# 19-Power-P5V.net
KiCad netlist of a schematic drawn in Altium Designer
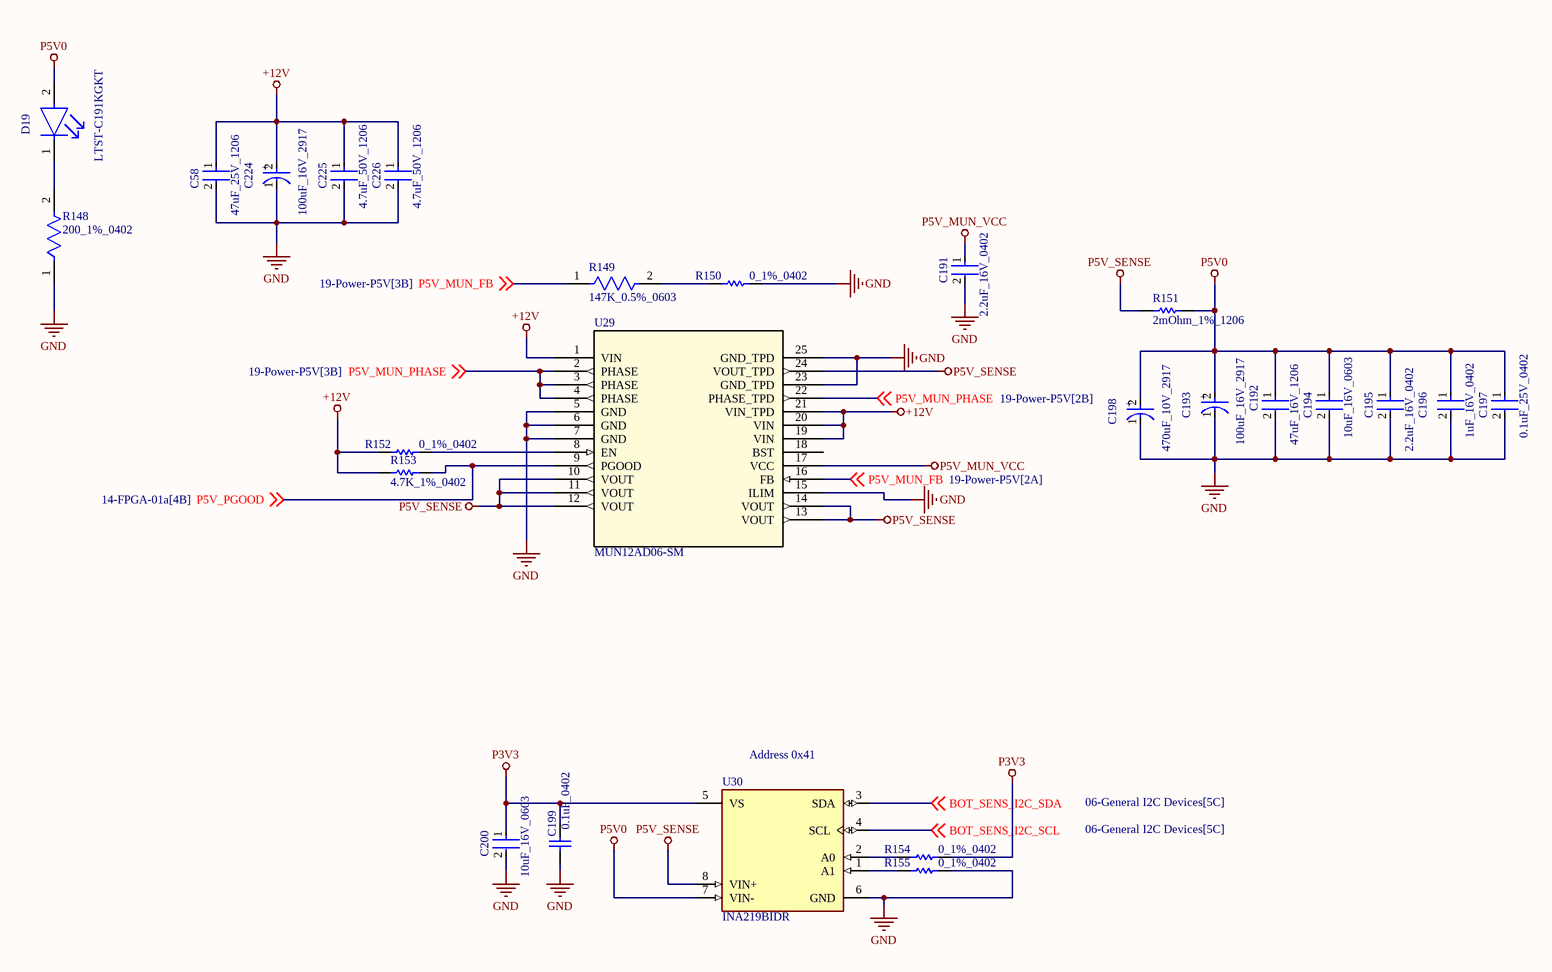
[diagram p0: 19-Power-P5V.SchDoc]

(export (version "E")
  (design (tool "Eeschema 10.0.6"))
  (components
    (comp (ref "C58")
      (value "47uF_25V_1206")
      (footprint "FP-C3216-160-0_2-MFG")
      (description "Multilayer Ceramic Capacitors 47uF ±20% 25V X5R SMD 1206")
      (fields (field (name "VOLTAGE") "25V") (field (name "TOLERANCE") "20%"))
      (libsource (lib "Altium Content Vault") (part "11868f565c42a9108669ba33697ecf6"))
    )
    (comp (ref "C191")
      (value "2.2uF_16V_0402")
      (footprint "FP-C1005-050-0_05-IPC_A")
      (description "Multilayer Ceramic Capacitors 2.2μF ±10% 16V X5R SMD 0402")
      (fields (field (name "TOLERANCE") "10%"))
      (libsource (lib "Altium Content Vault") (part "b4654b650e69147ec39a6b967a45e02"))
    )
    (comp (ref "C192")
      (value "47uF_16V_1206")
      (footprint "FP-C3216-160-0_2-MFG")
      (description "Multilayer Ceramic Capacitors 47uF ±20% 16V X5R SMD 1206")
      (fields (field (name "TOLERANCE") "20%"))
      (libsource (lib "Altium Content Vault") (part "11868f565c42a9108669ba33697ecf6"))
    )
    (comp (ref "C193")
      (value "100uF_16V_2917")
      (footprint "FP-T495D107K016ATE125-MFG")
      (description "CAP TANT 100UF 10% 16V 2917")
      (fields (field (name "VOLTAGE") "16V") (field (name "TOLERANCE") "10%"))
      (libsource (lib "Altium Content Vault") (part "a00bbbee19879c290e62620ae7e47b1"))
    )
    (comp (ref "C194")
      (value "10uF_16V_0603")
      (footprint "FP-0603-L_1_6_0_2-W_0_8_0-MFG")
      (description "Multilayer Ceramic Capacitor 10uF 16V X5R 20% SMD 0603 T/R")
      (fields (field (name "TOLERANCE") "20%"))
      (libsource (lib "Altium Content Vault") (part "b4654b650e69147ec39a6b967a45e02"))
    )
    (comp (ref "C195")
      (value "2.2uF_16V_0402")
      (footprint "FP-C1005-050-0_05-IPC_A")
      (description "Multilayer Ceramic Capacitors 2.2μF ±10% 16V X5R SMD 0402")
      (fields (field (name "TOLERANCE") "10%"))
      (libsource (lib "Altium Content Vault") (part "b4654b650e69147ec39a6b967a45e02"))
    )
    (comp (ref "C196")
      (value "1uF_16V_0402")
      (footprint "FP-0402-L_1_0_0_05-W_0_5-IPC_A")
      (description "None")
      (fields (field (name "TOLERANCE") "10%"))
      (libsource (lib "Altium Content Vault") (part "b4654b650e69147ec39a6b967a45e02"))
    )
    (comp (ref "C197")
      (value "0.1uF_25V_0402")
      (footprint "FP-0402-L_1_0_1-W_0_5_0_1-IPC_C")
      (description "General Purpose Ceramic Capacitor, 0402, 100nF, 10%, X7R, 15%, 25V")
      (fields (field (name "VOLTAGE") "25V") (field (name "TOLERANCE") "10%"))
      (libsource (lib "Altium Content Vault") (part "b4654b650e69147ec39a6b967a45e02"))
    )
    (comp (ref "C198")
      (value "470uF_10V_2917")
      (footprint "FP-TAJE-MFG")
      (description "470uF 10V  ±10% 500mΩ 2917  SMD Tantalum Capacitor")
      (fields (field (name "TOLERANCE") "10%") (field (name "VOLTAGE") "10V"))
      (libsource (lib "Altium Content Vault") (part "203bc49f2ac43e59fd269a8c329ed05"))
    )
    (comp (ref "C199")
      (value "0.1uF_0402")
      (footprint "CAPC1005X56X25NL10T15")
      (fields
        (field (name "PART NUMBER") "LD02YD104KAB2A")
        (field (name "MANUFACTURER") "AVX Interconnect / Elco")
      )
      (libsource (lib "Altium Content Vault") (part "CAP"))
    )
    (comp (ref "C200")
      (value "10uF_16V_0603")
      (footprint "FP-0603-L_1_6_0_2-W_0_8_0-MFG")
      (description "Multilayer Ceramic Capacitor 10uF 16V X5R 20% SMD 0603 T/R")
      (fields (field (name "TOLERANCE") "20%"))
      (libsource (lib "Altium Content Vault") (part "b4654b650e69147ec39a6b967a45e02"))
    )
    (comp (ref "C224")
      (value "100uF_16V_2917")
      (footprint "FP-T495D107K016ATE125-MFG")
      (description "CAP TANT 100UF 10% 16V 2917")
      (fields (field (name "VOLTAGE") "16V") (field (name "TOLERANCE") "10%"))
      (libsource (lib "Altium Content Vault") (part "a00bbbee19879c290e62620ae7e47b1"))
    )
    (comp (ref "C225")
      (value "4.7uF_50V_1206")
      (footprint "FP-GRM31C-0_2-e0_3_0_8-IPC_C")
      (description "Chip Multilayer Ceramic Capacitors for General Purpose, 1206, 4.7uF, X7R, 15%, 10%, 50V")
      (fields (field (name "VOLTAGE") "50V") (field (name "TOLERANCE") "10%"))
      (libsource (lib "Altium Content Vault") (part "02cd4be3c70576c341d710602a673aa"))
    )
    (comp (ref "C226")
      (value "4.7uF_50V_1206")
      (footprint "FP-GRM31C-0_2-e0_3_0_8-IPC_C")
      (description "Chip Multilayer Ceramic Capacitors for General Purpose, 1206, 4.7uF, X7R, 15%, 10%, 50V")
      (fields (field (name "VOLTAGE") "50V") (field (name "TOLERANCE") "10%"))
      (libsource (lib "Altium Content Vault") (part "02cd4be3c70576c341d710602a673aa"))
    )
    (comp (ref "D19")
      (value "LTST-C191KGKT")
      (footprint "FP-LTST-C191KGKT-MFG")
      (description "LED GREEN CLEAR SMD")
      (libsource (lib "Altium Content Vault") (part "8706943c75ba83719d021d2fdc84c58"))
    )
    (comp (ref "R148")
      (value "200_1%_0402")
      (footprint "FP-ERJ2RK-IPC_A")
      (description "RES SMD 200 OHM 1% 1/10W 0402")
      (fields (field (name "TOLERANCE") "1%"))
      (libsource (lib "Altium Content Vault") (part "1029c3af85768c4190bb7ad29bc67b5"))
    )
    (comp (ref "R149")
      (value "147K_0.5%_0603")
      (footprint "FP-RR0816-IPC_C")
      (description "147kΩ ±0.5% 0.0625W 1/16W Chip Resistor 0603 (1608 Metric) Thin Film")
      (fields (field (name "TOLERANCE") "0.5%"))
      (libsource (lib "Altium Content Vault") (part "1029c3af85768c4190bb7ad29bc67b5"))
    )
    (comp (ref "R150")
      (value "0_1%_0402")
      (footprint "RESC1005X40X25LL05T05")
      (description "Chip Resistor, 0 Ohm, 0.1 W, -55 to 155 degC, 0402 (1005 Metric), RoHS, Tape and Reel")
      (fields (field (name "MANUFACTURER") "Panasonic") (field (name "TOLERANCE") "5%"))
      (libsource (lib "Altium Content Vault") (part "RES-2"))
    )
    (comp (ref "R151")
      (value "2mOhm_1%_1206")
      (footprint "RESC3216X89X64NL25T25")
      (fields (field (name "MANUFACTURER") "Vishay Dale") (field (name "PART NUMBER") "WSL12062L000FEA18"))
      (libsource (lib "Altium Content Vault") (part "RES"))
    )
    (comp (ref "R152")
      (value "0_1%_0402")
      (footprint "RESC1005X40X25LL05T05")
      (description "Chip Resistor, 0 Ohm, 0.1 W, -55 to 155 degC, 0402 (1005 Metric), RoHS, Tape and Reel")
      (fields (field (name "MANUFACTURER") "Panasonic") (field (name "TOLERANCE") "5%"))
      (libsource (lib "Altium Content Vault") (part "RES-2"))
    )
    (comp (ref "R153")
      (value "4.7K_1%_0402")
      (footprint "RESC1005X40X25NL10T10")
      (fields (field (name "MANUFACTURER") "Bourns") (field (name "PART NUMBER") "CR0402-FX-4701GLF"))
      (libsource (lib "Altium Content Vault") (part "RES"))
    )
    (comp (ref "R154")
      (value "0_1%_0402")
      (footprint "RESC1005X40X25LL05T05")
      (description "Chip Resistor, 0 Ohm, 0.1 W, -55 to 155 degC, 0402 (1005 Metric), RoHS, Tape and Reel")
      (fields (field (name "MANUFACTURER") "Panasonic") (field (name "TOLERANCE") "5%"))
      (libsource (lib "Altium Content Vault") (part "RES-2"))
    )
    (comp (ref "R155")
      (value "0_1%_0402")
      (footprint "RESC1005X40X25LL05T05")
      (description "Chip Resistor, 0 Ohm, 0.1 W, -55 to 155 degC, 0402 (1005 Metric), RoHS, Tape and Reel")
      (fields (field (name "MANUFACTURER") "Panasonic") (field (name "TOLERANCE") "5%"))
      (libsource (lib "Altium Content Vault") (part "RES-2"))
    )
    (comp (ref "U29")
      (value "MUN12AD06-SM")
      (footprint "MUN12AD06-SM_CYN")
      (description "No Description Available")
      (libsource (lib "MUN12AD06-SM") (part "MUN12AD06-SM"))
    )
    (comp (ref "U30")
      (value "INA219BIDR")
      (footprint "FP-D0008A-MFG")
      (description "IC MONITOR PWR/CURR BIDIR 8-SOIC")
      (libsource (lib "Altium Content Vault") (part "41cc1aee4cbc9fa2660a15773fa0e79"))
    )
  )
  (nets
    (net (code "1") (name "+12V") (class "Default")
      (node (ref "C224") (pin "2") (pinfunction "A_2") (pintype "passive"))
      (node (ref "C225") (pin "1") (pinfunction "1_1") (pintype "passive"))
      (node (ref "C226") (pin "1") (pinfunction "1_1") (pintype "passive"))
      (node (ref "C58") (pin "1") (pinfunction "1_1") (pintype "passive"))
      (node (ref "R152") (pin "1") (pinfunction "1_1") (pintype "passive"))
      (node (ref "R153") (pin "2") (pinfunction "2_2") (pintype "passive"))
      (node (ref "U29") (pin "1") (pinfunction "VIN_1") (pintype "power_in"))
      (node (ref "U29") (pin "19") (pinfunction "VIN_19") (pintype "power_in"))
      (node (ref "U29") (pin "20") (pinfunction "VIN_20") (pintype "power_in"))
      (node (ref "U29") (pin "21") (pinfunction "VIN_TPD_21") (pintype "power_in"))
    )
    (net (code "2") (name "BOT_SENS_I2C_SCL") (class "Default")
      (node (ref "U30") (pin "4") (pinfunction "SCL_4") (pintype "bidirectional"))
    )
    (net (code "3") (name "BOT_SENS_I2C_SDA") (class "Default")
      (node (ref "U30") (pin "3") (pinfunction "SDA_3") (pintype "bidirectional"))
    )
    (net (code "4") (name "GND") (class "Default")
      (node (ref "C191") (pin "2") (pinfunction "2_2") (pintype "passive"))
      (node (ref "C192") (pin "2") (pinfunction "2_2") (pintype "passive"))
      (node (ref "C193") (pin "1") (pinfunction "C_1") (pintype "passive"))
      (node (ref "C194") (pin "2") (pinfunction "2_2") (pintype "passive"))
      (node (ref "C195") (pin "2") (pinfunction "2_2") (pintype "passive"))
      (node (ref "C196") (pin "2") (pinfunction "2_2") (pintype "passive"))
      (node (ref "C197") (pin "2") (pinfunction "2_2") (pintype "passive"))
      (node (ref "C198") (pin "1") (pinfunction "C_1") (pintype "passive"))
      (node (ref "C199") (pin "1") (pinfunction "1_1") (pintype "passive"))
      (node (ref "C200") (pin "2") (pinfunction "2_2") (pintype "passive"))
      (node (ref "C224") (pin "1") (pinfunction "C_1") (pintype "passive"))
      (node (ref "C225") (pin "2") (pinfunction "2_2") (pintype "passive"))
      (node (ref "C226") (pin "2") (pinfunction "2_2") (pintype "passive"))
      (node (ref "C58") (pin "2") (pinfunction "2_2") (pintype "passive"))
      (node (ref "R148") (pin "1") (pinfunction "1_1") (pintype "passive"))
      (node (ref "R150") (pin "2") (pinfunction "2_2") (pintype "passive"))
      (node (ref "R155") (pin "2") (pinfunction "2_2") (pintype "passive"))
      (node (ref "U29") (pin "15") (pinfunction "ILIM_15") (pintype "passive"))
      (node (ref "U29") (pin "23") (pinfunction "GND_TPD_23") (pintype "power_in"))
      (node (ref "U29") (pin "25") (pinfunction "GND_TPD_25") (pintype "power_in"))
      (node (ref "U29") (pin "5") (pinfunction "GND_5") (pintype "power_in"))
      (node (ref "U29") (pin "6") (pinfunction "GND_6") (pintype "power_in"))
      (node (ref "U29") (pin "7") (pinfunction "GND_7") (pintype "power_in"))
      (node (ref "U30") (pin "6") (pinfunction "GND_6") (pintype "power_in"))
    )
    (net (code "5") (name "Net-(D19-C)") (class "Default")
      (node (ref "D19") (pin "1") (pinfunction "C_1") (pintype "passive"))
      (node (ref "R148") (pin "2") (pinfunction "2_2") (pintype "passive"))
    )
    (net (code "6") (name "Net-(R149-Pad2)") (class "Default")
      (node (ref "R149") (pin "2") (pinfunction "2_2") (pintype "passive"))
      (node (ref "R150") (pin "1") (pinfunction "1_1") (pintype "passive"))
    )
    (net (code "7") (name "Net-(U29-EN)") (class "Default")
      (node (ref "R152") (pin "2") (pinfunction "2_2") (pintype "passive"))
      (node (ref "U29") (pin "8") (pinfunction "EN_8") (pintype "input"))
    )
    (net (code "8") (name "Net-(U30-A0)") (class "Default")
      (node (ref "R154") (pin "1") (pinfunction "1_1") (pintype "passive"))
      (node (ref "U30") (pin "2") (pinfunction "A0_2") (pintype "input"))
    )
    (net (code "9") (name "Net-(U30-A1)") (class "Default")
      (node (ref "R155") (pin "1") (pinfunction "1_1") (pintype "passive"))
      (node (ref "U30") (pin "1") (pinfunction "A1_1") (pintype "input"))
    )
    (net (code "10") (name "P3V3") (class "Default")
      (node (ref "C199") (pin "2") (pinfunction "2_2") (pintype "passive"))
      (node (ref "C200") (pin "1") (pinfunction "1_1") (pintype "passive"))
      (node (ref "R154") (pin "2") (pinfunction "2_2") (pintype "passive"))
      (node (ref "U30") (pin "5") (pinfunction "VS_5") (pintype "power_in"))
    )
    (net (code "11") (name "P5V0") (class "Default")
      (node (ref "C192") (pin "1") (pinfunction "1_1") (pintype "passive"))
      (node (ref "C193") (pin "2") (pinfunction "A_2") (pintype "passive"))
      (node (ref "C194") (pin "1") (pinfunction "1_1") (pintype "passive"))
      (node (ref "C195") (pin "1") (pinfunction "1_1") (pintype "passive"))
      (node (ref "C196") (pin "1") (pinfunction "1_1") (pintype "passive"))
      (node (ref "C197") (pin "1") (pinfunction "1_1") (pintype "passive"))
      (node (ref "C198") (pin "2") (pinfunction "A_2") (pintype "passive"))
      (node (ref "D19") (pin "2") (pinfunction "A_2") (pintype "passive"))
      (node (ref "R151") (pin "2") (pinfunction "2_2") (pintype "passive"))
      (node (ref "U30") (pin "7") (pinfunction "VIN-_7") (pintype "input"))
    )
    (net (code "12") (name "P5V_MUN_FB") (class "Default")
      (node (ref "R149") (pin "1") (pinfunction "1_1") (pintype "passive"))
      (node (ref "U29") (pin "16") (pinfunction "FB_16") (pintype "input"))
    )
    (net (code "13") (name "P5V_MUN_PHASE") (class "Default")
      (node (ref "U29") (pin "2") (pinfunction "PHASE_2") (pintype "output"))
      (node (ref "U29") (pin "22") (pinfunction "PHASE_TPD_22") (pintype "output"))
      (node (ref "U29") (pin "3") (pinfunction "PHASE_3") (pintype "output"))
      (node (ref "U29") (pin "4") (pinfunction "PHASE_4") (pintype "output"))
    )
    (net (code "14") (name "P5V_MUN_VCC") (class "Default")
      (node (ref "C191") (pin "1") (pinfunction "1_1") (pintype "passive"))
      (node (ref "U29") (pin "17") (pinfunction "VCC_17") (pintype "power_in"))
    )
    (net (code "15") (name "P5V_PGOOD") (class "Default")
      (node (ref "R153") (pin "1") (pinfunction "1_1") (pintype "passive"))
      (node (ref "U29") (pin "9") (pinfunction "PGOOD_9") (pintype "output"))
    )
    (net (code "16") (name "P5V_SENSE") (class "Default")
      (node (ref "R151") (pin "1") (pinfunction "1_1") (pintype "passive"))
      (node (ref "U29") (pin "10") (pinfunction "VOUT_10") (pintype "output"))
      (node (ref "U29") (pin "11") (pinfunction "VOUT_11") (pintype "output"))
      (node (ref "U29") (pin "12") (pinfunction "VOUT_12") (pintype "output"))
      (node (ref "U29") (pin "13") (pinfunction "VOUT_13") (pintype "output"))
      (node (ref "U29") (pin "14") (pinfunction "VOUT_14") (pintype "output"))
      (node (ref "U29") (pin "24") (pinfunction "VOUT_TPD_24") (pintype "output"))
      (node (ref "U30") (pin "8") (pinfunction "VIN+_8") (pintype "input"))
    )
    (net (code "17") (name "unconnected-(U29-BST-Pad18)") (class "Default")
      (node (ref "U29") (pin "18") (pinfunction "BST_18") (pintype "power_in"))
    )
  )
)
